# ws2812B.net
KiCad netlist of a schematic drawn in EAGLE
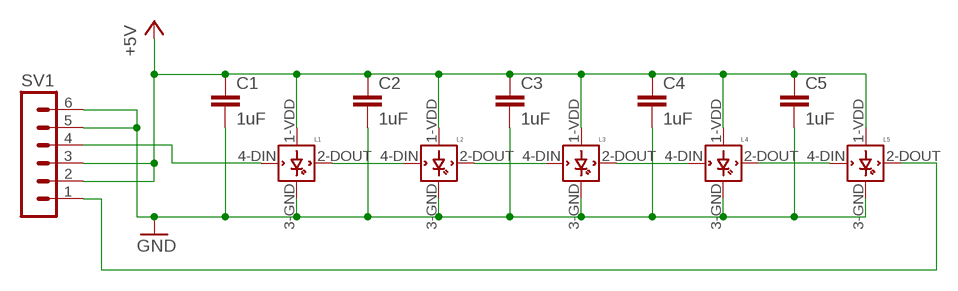
[diagram p0: schematic, sheet 1]

(export (version "E")
  (design (tool "Eeschema 10.0.6"))
  (components
    (comp (ref "C1")
      (value "1uF")
      (footprint "eagle-import:C10B4")
      (libsource (lib "eagle-import") (part "C10/4"))
    )
    (comp (ref "C2")
      (value "1uF")
      (footprint "eagle-import:C10B4")
      (libsource (lib "eagle-import") (part "C10/4"))
    )
    (comp (ref "C3")
      (value "1uF")
      (footprint "eagle-import:C10B4")
      (libsource (lib "eagle-import") (part "C10/4"))
    )
    (comp (ref "C4")
      (value "1uF")
      (footprint "eagle-import:C10B4")
      (libsource (lib "eagle-import") (part "C10/4"))
    )
    (comp (ref "C5")
      (value "1uF")
      (footprint "eagle-import:C10B4")
      (libsource (lib "eagle-import") (part "C10/4"))
    )
    (comp (ref "L1")
      (value "WS2812B")
      (footprint "eagle-import:WS2812B")
      (libsource (lib "eagle-import") (part "WS2812B"))
    )
    (comp (ref "L2")
      (value "WS2812B")
      (footprint "eagle-import:WS2812B")
      (libsource (lib "eagle-import") (part "WS2812B"))
    )
    (comp (ref "L3")
      (value "WS2812B")
      (footprint "eagle-import:WS2812B")
      (libsource (lib "eagle-import") (part "WS2812B"))
    )
    (comp (ref "L4")
      (value "WS2812B")
      (footprint "eagle-import:WS2812B")
      (libsource (lib "eagle-import") (part "WS2812B"))
    )
    (comp (ref "L5")
      (value "WS2812B")
      (footprint "eagle-import:WS2812B")
      (libsource (lib "eagle-import") (part "WS2812B"))
    )
    (comp (ref "SV1")
      (value "MA06-1")
      (footprint "eagle-import:MA06-1")
      (libsource (lib "eagle-import") (part "MA06-1"))
    )
  )
  (nets
    (net (code "1") (name "+5V") (class "Default")
      (node (ref "C1") (pin "1") (pinfunction "1_1") (pintype "passive"))
      (node (ref "C2") (pin "1") (pinfunction "1_1") (pintype "passive"))
      (node (ref "C3") (pin "1") (pinfunction "1_1") (pintype "passive"))
      (node (ref "C4") (pin "1") (pinfunction "1_1") (pintype "passive"))
      (node (ref "C5") (pin "1") (pinfunction "1_1") (pintype "passive"))
      (node (ref "L1") (pin "1-VDD") (pinfunction "VDD_1-VDD") (pintype "bidirectional"))
      (node (ref "L2") (pin "1-VDD") (pinfunction "VDD_1-VDD") (pintype "bidirectional"))
      (node (ref "L3") (pin "1-VDD") (pinfunction "VDD_1-VDD") (pintype "bidirectional"))
      (node (ref "L4") (pin "1-VDD") (pinfunction "VDD_1-VDD") (pintype "bidirectional"))
      (node (ref "L5") (pin "1-VDD") (pinfunction "VDD_1-VDD") (pintype "bidirectional"))
      (node (ref "SV1") (pin "2") (pinfunction "2_2") (pintype "passive"))
      (node (ref "SV1") (pin "3") (pinfunction "3_3") (pintype "passive"))
    )
    (net (code "2") (name "GND") (class "Default")
      (node (ref "C1") (pin "2") (pinfunction "2_2") (pintype "passive"))
      (node (ref "C2") (pin "2") (pinfunction "2_2") (pintype "passive"))
      (node (ref "C3") (pin "2") (pinfunction "2_2") (pintype "passive"))
      (node (ref "C4") (pin "2") (pinfunction "2_2") (pintype "passive"))
      (node (ref "C5") (pin "2") (pinfunction "2_2") (pintype "passive"))
      (node (ref "L1") (pin "3-GND") (pinfunction "GND_3-GND") (pintype "bidirectional"))
      (node (ref "L2") (pin "3-GND") (pinfunction "GND_3-GND") (pintype "bidirectional"))
      (node (ref "L3") (pin "3-GND") (pinfunction "GND_3-GND") (pintype "bidirectional"))
      (node (ref "L4") (pin "3-GND") (pinfunction "GND_3-GND") (pintype "bidirectional"))
      (node (ref "L5") (pin "3-GND") (pinfunction "GND_3-GND") (pintype "bidirectional"))
      (node (ref "SV1") (pin "5") (pinfunction "5_5") (pintype "passive"))
      (node (ref "SV1") (pin "6") (pinfunction "6_6") (pintype "passive"))
    )
    (net (code "3") (name "Net-(L1-DIN)") (class "Default")
      (node (ref "L1") (pin "4-DIN") (pinfunction "DIN_4-DIN") (pintype "input"))
      (node (ref "SV1") (pin "4") (pinfunction "4_4") (pintype "passive"))
    )
    (net (code "4") (name "Net-(L1-DOUT)") (class "Default")
      (node (ref "L1") (pin "2-DOUT") (pinfunction "DOUT_2-DOUT") (pintype "output"))
      (node (ref "L2") (pin "4-DIN") (pinfunction "DIN_4-DIN") (pintype "input"))
    )
    (net (code "5") (name "Net-(L2-DOUT)") (class "Default")
      (node (ref "L2") (pin "2-DOUT") (pinfunction "DOUT_2-DOUT") (pintype "output"))
      (node (ref "L3") (pin "4-DIN") (pinfunction "DIN_4-DIN") (pintype "input"))
    )
    (net (code "6") (name "Net-(L3-DOUT)") (class "Default")
      (node (ref "L3") (pin "2-DOUT") (pinfunction "DOUT_2-DOUT") (pintype "output"))
      (node (ref "L4") (pin "4-DIN") (pinfunction "DIN_4-DIN") (pintype "input"))
    )
    (net (code "7") (name "Net-(L4-DOUT)") (class "Default")
      (node (ref "L4") (pin "2-DOUT") (pinfunction "DOUT_2-DOUT") (pintype "output"))
      (node (ref "L5") (pin "4-DIN") (pinfunction "DIN_4-DIN") (pintype "input"))
    )
    (net (code "8") (name "Net-(L5-DOUT)") (class "Default")
      (node (ref "L5") (pin "2-DOUT") (pinfunction "DOUT_2-DOUT") (pintype "output"))
      (node (ref "SV1") (pin "1") (pinfunction "1_1") (pintype "passive"))
    )
  )
)
